# schemFinal.net
KiCad netlist of a schematic drawn in EAGLE
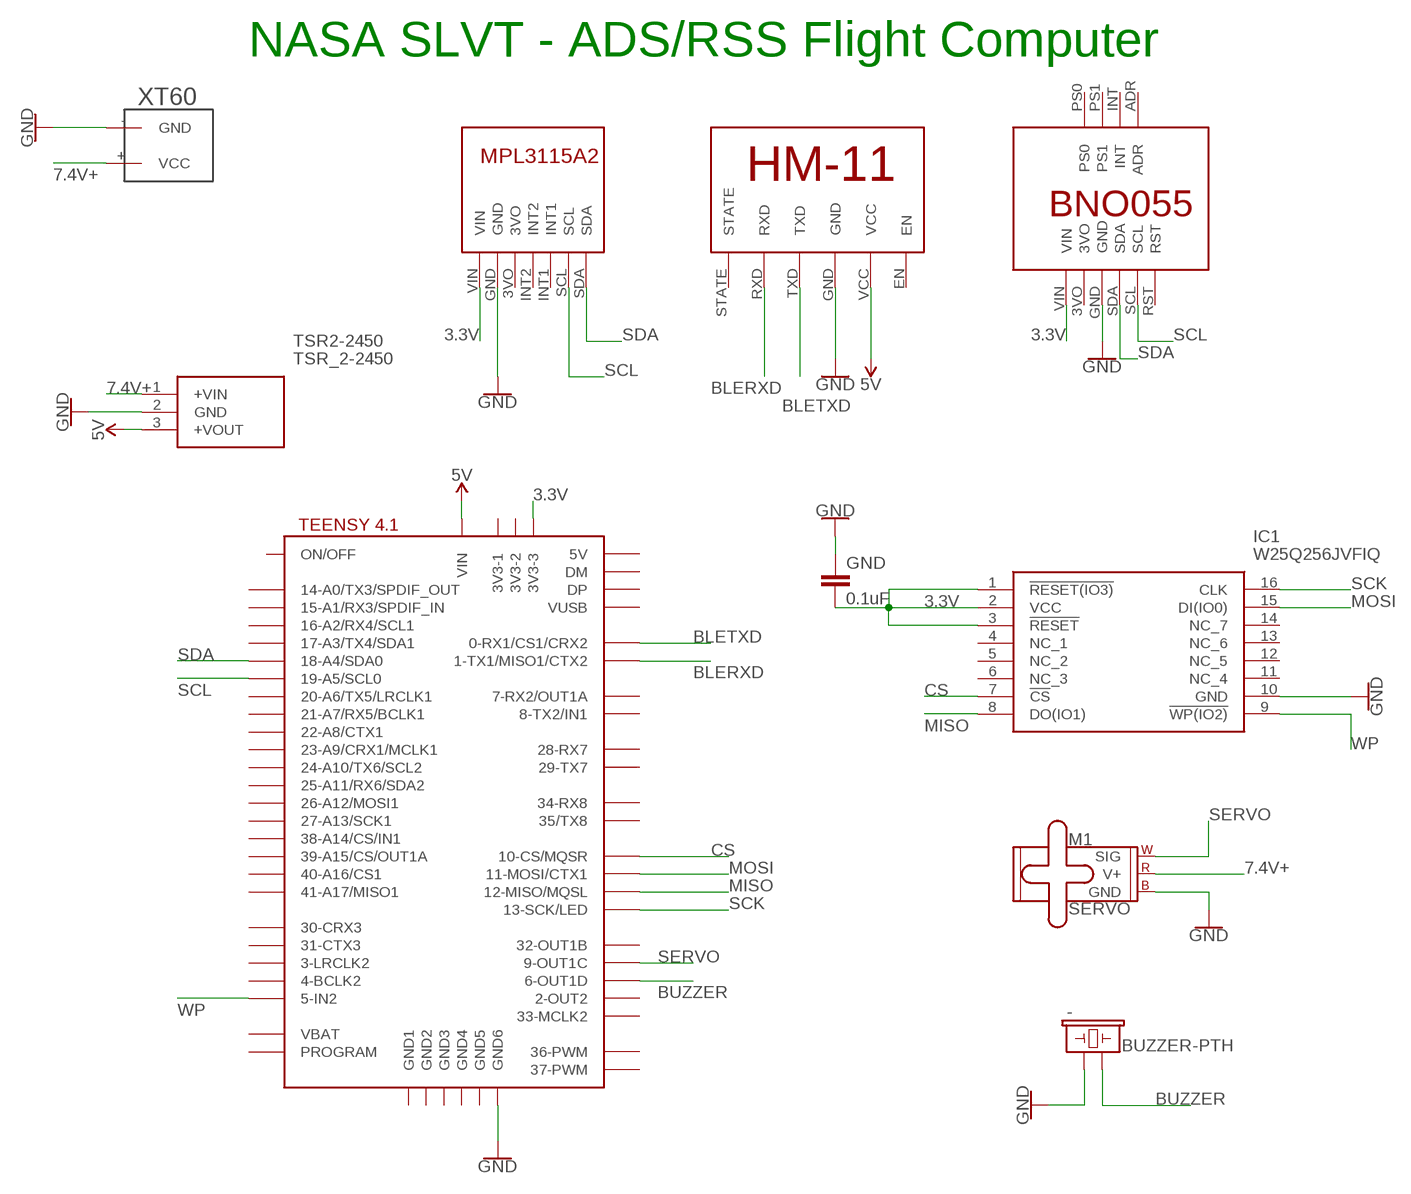
[diagram p0: schematic, sheet 1]

(export (version "E")
  (design (tool "Eeschema 10.0.6"))
  (components
    (comp (ref "-")
      (value "BUZZER-PTH")
      (footprint "eagle-import:BUZZER-12MM")
      (libsource (lib "eagle-import") (part "BUZZER-PTH"))
    )
    (comp (ref "GND")
      (value "0.1uF")
      (footprint "eagle-import:CAP-PTH-2.54")
      (libsource (lib "eagle-import") (part "22PF-PTH-2.54MM-200V-5%"))
    )
    (comp (ref "IC1")
      (value "W25Q256JVFIQ")
      (footprint "eagle-import:SOIC127P1032X264-16N")
      (fields (field (name "MOUSER_PART_NUMBER") "454-W25Q256JVFIQ"))
      (libsource (lib "eagle-import") (part "W25Q256JVFIQ"))
    )
    (comp (ref "M1")
      (value "SERVO")
      (footprint "eagle-import:1X03")
      (libsource (lib "eagle-import") (part "SERVO"))
    )
    (comp (ref "TSR2-2450")
      (value "TSR_2-2450")
      (footprint "eagle-import:TSR-2")
      (fields
        (field (name "MANUFACTURER_PART_NUMBER") "TSR 2-2450")
        (field (name "MOUSER_PART_NUMBER") "495-TSR2-2450")
      )
      (libsource (lib "eagle-import") (part "TSR_2-2450"))
    )
    (comp (ref "U$1")
      (value "BNO055")
      (footprint "eagle-import:BNO055")
      (libsource (lib "eagle-import") (part "BNO055"))
    )
    (comp (ref "U$2")
      (value "MPL3115A2")
      (footprint "eagle-import:MPL3115A2")
      (libsource (lib "eagle-import") (part "MPL3115A2"))
    )
    (comp (ref "U$3")
      (value "TEENSY41-E")
      (footprint "eagle-import:TENNSY41-E")
      (libsource (lib "eagle-import") (part "TEENSY41-E"))
    )
    (comp (ref "U$4")
      (value "HM-11")
      (footprint "eagle-import:HM-11")
      (libsource (lib "eagle-import") (part "HM-11"))
    )
    (comp (ref "U$5")
      (value "XT60")
      (footprint "eagle-import:XT60")
      (libsource (lib "eagle-import") (part "XT60"))
    )
  )
  (nets
    (net (code "1") (name "/3.3V") (class "Default")
      (node (ref "GND") (pin "2") (pinfunction "2_2") (pintype "passive"))
      (node (ref "IC1") (pin "1") (pinfunction "~{RESET(IO3})_1") (pintype "bidirectional"))
      (node (ref "IC1") (pin "2") (pinfunction "VCC_2") (pintype "bidirectional"))
      (node (ref "IC1") (pin "3") (pinfunction "~{RESET}_3") (pintype "bidirectional"))
      (node (ref "U$1") (pin "VIN") (pinfunction "VIN_VIN") (pintype "bidirectional"))
      (node (ref "U$2") (pin "VIN") (pinfunction "VIN_VIN") (pintype "bidirectional"))
      (node (ref "U$3") (pin "3V3-3") (pinfunction "3V3-3_3V3-3") (pintype "bidirectional"))
    )
    (net (code "2") (name "/7.4V+") (class "Default")
      (node (ref "M1") (pin "2") (pinfunction "V+_2") (pintype "bidirectional"))
      (node (ref "TSR2-2450") (pin "1") (pinfunction "+VIN_1") (pintype "input"))
      (node (ref "U$5") (pin "+") (pinfunction "VCC_+") (pintype "bidirectional"))
    )
    (net (code "3") (name "/BLERXD") (class "Default")
      (node (ref "U$3") (pin "1-TX1/MISO1/CTX2") (pinfunction "1-TX1/MISO1/CTX2_1-TX1/MISO1/CTX2") (pintype "bidirectional"))
      (node (ref "U$4") (pin "RXD") (pinfunction "RXD_RXD") (pintype "bidirectional"))
    )
    (net (code "4") (name "/BLETXD") (class "Default")
      (node (ref "U$3") (pin "0-RX1/CS1/CRX2") (pinfunction "0-RX1/CS1/CRX2_0-RX1/CS1/CRX2") (pintype "bidirectional"))
      (node (ref "U$4") (pin "TXD") (pinfunction "TXD_TXD") (pintype "bidirectional"))
    )
    (net (code "5") (name "/BUZZER") (class "Default")
      (node (ref "-") (pin "-") (pinfunction "2_-") (pintype "passive"))
      (node (ref "U$3") (pin "6-OUT1D") (pinfunction "6-OUT1D_6-OUT1D") (pintype "bidirectional"))
    )
    (net (code "6") (name "/CS") (class "Default")
      (node (ref "IC1") (pin "7") (pinfunction "~{CS}_7") (pintype "bidirectional"))
      (node (ref "U$3") (pin "10-CS\\MQSR") (pinfunction "10-CS/MQSR_10-CS\\MQSR") (pintype "bidirectional"))
    )
    (net (code "7") (name "/MISO") (class "Default")
      (node (ref "IC1") (pin "8") (pinfunction "DO(IO1)_8") (pintype "bidirectional"))
      (node (ref "U$3") (pin "12-MISO/MQSL") (pinfunction "12-MISO/MQSL_12-MISO/MQSL") (pintype "bidirectional"))
    )
    (net (code "8") (name "/MOSI") (class "Default")
      (node (ref "IC1") (pin "15") (pinfunction "DI(IO0)_15") (pintype "bidirectional"))
      (node (ref "U$3") (pin "11-MOSI/CTX1") (pinfunction "11-MOSI/CTX1_11-MOSI/CTX1") (pintype "bidirectional"))
    )
    (net (code "9") (name "/SCK") (class "Default")
      (node (ref "IC1") (pin "16") (pinfunction "CLK_16") (pintype "bidirectional"))
      (node (ref "U$3") (pin "13-SCK/LED") (pinfunction "13-SCK/LED_13-SCK/LED") (pintype "bidirectional"))
    )
    (net (code "10") (name "/SCL") (class "Default")
      (node (ref "U$1") (pin "SCL") (pinfunction "SCL_SCL") (pintype "bidirectional"))
      (node (ref "U$2") (pin "SCL") (pinfunction "SCL_SCL") (pintype "bidirectional"))
      (node (ref "U$3") (pin "19-A5/SCL0") (pinfunction "19-A5/SCL0_19-A5/SCL0") (pintype "bidirectional"))
    )
    (net (code "11") (name "/SDA") (class "Default")
      (node (ref "U$1") (pin "SDA") (pinfunction "SDA_SDA") (pintype "bidirectional"))
      (node (ref "U$2") (pin "SDA") (pinfunction "SDA_SDA") (pintype "bidirectional"))
      (node (ref "U$3") (pin "18-A4/SDA0") (pinfunction "18-A4/SDA0_18-A4/SDA0") (pintype "bidirectional"))
    )
    (net (code "12") (name "/SERVO") (class "Default")
      (node (ref "M1") (pin "1") (pinfunction "SIG_1") (pintype "bidirectional"))
      (node (ref "U$3") (pin "9-OUT1C") (pinfunction "9-OUT1C_9-OUT1C") (pintype "bidirectional"))
    )
    (net (code "13") (name "/WP") (class "Default")
      (node (ref "IC1") (pin "9") (pinfunction "~{WP(IO2})_9") (pintype "bidirectional"))
      (node (ref "U$3") (pin "5-IN2") (pinfunction "5-IN2_5-IN2") (pintype "bidirectional"))
    )
    (net (code "14") (name "5V") (class "Default")
      (node (ref "TSR2-2450") (pin "3") (pinfunction "+VOUT_3") (pintype "output"))
      (node (ref "U$3") (pin "VIN") (pinfunction "VIN_VIN") (pintype "bidirectional"))
      (node (ref "U$4") (pin "VCC") (pinfunction "VCC_VCC") (pintype "bidirectional"))
    )
    (net (code "15") (name "GND") (class "Default")
      (node (ref "-") (pin "+") (pinfunction "1_+") (pintype "passive"))
      (node (ref "GND") (pin "1") (pinfunction "1_1") (pintype "passive"))
      (node (ref "IC1") (pin "10") (pinfunction "GND_10") (pintype "bidirectional"))
      (node (ref "M1") (pin "3") (pinfunction "GND_3") (pintype "bidirectional"))
      (node (ref "TSR2-2450") (pin "2") (pinfunction "GND_2") (pintype "power_in"))
      (node (ref "U$1") (pin "GND") (pinfunction "GND_GND") (pintype "bidirectional"))
      (node (ref "U$2") (pin "GND") (pinfunction "GND_GND") (pintype "bidirectional"))
      (node (ref "U$3") (pin "GND6") (pinfunction "GND6_GND6") (pintype "bidirectional"))
      (node (ref "U$4") (pin "GND") (pinfunction "GND_GND") (pintype "bidirectional"))
      (node (ref "U$5") (pin "-") (pinfunction "GND_-") (pintype "bidirectional"))
    )
    (net (code "16") (name "unconnected-(IC1-NC_1-Pad4)") (class "Default")
      (node (ref "IC1") (pin "4") (pinfunction "NC_1_4") (pintype "bidirectional"))
    )
    (net (code "17") (name "unconnected-(IC1-NC_2-Pad5)") (class "Default")
      (node (ref "IC1") (pin "5") (pinfunction "NC_2_5") (pintype "bidirectional"))
    )
    (net (code "18") (name "unconnected-(IC1-NC_3-Pad6)") (class "Default")
      (node (ref "IC1") (pin "6") (pinfunction "NC_3_6") (pintype "bidirectional"))
    )
    (net (code "19") (name "unconnected-(IC1-NC_4-Pad11)") (class "Default")
      (node (ref "IC1") (pin "11") (pinfunction "NC_4_11") (pintype "bidirectional"))
    )
    (net (code "20") (name "unconnected-(IC1-NC_5-Pad12)") (class "Default")
      (node (ref "IC1") (pin "12") (pinfunction "NC_5_12") (pintype "bidirectional"))
    )
    (net (code "21") (name "unconnected-(IC1-NC_6-Pad13)") (class "Default")
      (node (ref "IC1") (pin "13") (pinfunction "NC_6_13") (pintype "bidirectional"))
    )
    (net (code "22") (name "unconnected-(IC1-NC_7-Pad14)") (class "Default")
      (node (ref "IC1") (pin "14") (pinfunction "NC_7_14") (pintype "bidirectional"))
    )
    (net (code "23") (name "unconnected-(U$1-Pad3VO)") (class "Default")
      (node (ref "U$1") (pin "3VO") (pinfunction "3VO_3VO") (pintype "bidirectional"))
    )
    (net (code "24") (name "unconnected-(U$1-PadADR)") (class "Default")
      (node (ref "U$1") (pin "ADR") (pinfunction "ADR_ADR") (pintype "bidirectional"))
    )
    (net (code "25") (name "unconnected-(U$1-PadINT)") (class "Default")
      (node (ref "U$1") (pin "INT") (pinfunction "INT_INT") (pintype "bidirectional"))
    )
    (net (code "26") (name "unconnected-(U$1-PadPS0)") (class "Default")
      (node (ref "U$1") (pin "PS0") (pinfunction "PS0_PS0") (pintype "bidirectional"))
    )
    (net (code "27") (name "unconnected-(U$1-PadPS1)") (class "Default")
      (node (ref "U$1") (pin "PS1") (pinfunction "PS1_PS1") (pintype "bidirectional"))
    )
    (net (code "28") (name "unconnected-(U$1-PadRST)") (class "Default")
      (node (ref "U$1") (pin "RST") (pinfunction "RST_RST") (pintype "bidirectional"))
    )
    (net (code "29") (name "unconnected-(U$2-Pad3VO)") (class "Default")
      (node (ref "U$2") (pin "3VO") (pinfunction "3VO_3VO") (pintype "bidirectional"))
    )
    (net (code "30") (name "unconnected-(U$2-PadINT1)") (class "Default")
      (node (ref "U$2") (pin "INT1") (pinfunction "INT1_INT1") (pintype "bidirectional"))
    )
    (net (code "31") (name "unconnected-(U$2-PadINT2)") (class "Default")
      (node (ref "U$2") (pin "INT2") (pinfunction "INT2_INT2") (pintype "bidirectional"))
    )
    (net (code "32") (name "unconnected-(U$3-5V-Pad+5V)") (class "Default")
      (node (ref "U$3") (pin "+5V") (pinfunction "5V_+5V") (pintype "bidirectional"))
    )
    (net (code "33") (name "unconnected-(U$3-35{slash}TX8-Pad35-TX8)") (class "Default")
      (node (ref "U$3") (pin "35-TX8") (pinfunction "35/TX8_35-TX8") (pintype "bidirectional"))
    )
    (net (code "34") (name "unconnected-(U$3-Pad2-OUT2)") (class "Default")
      (node (ref "U$3") (pin "2-OUT2") (pinfunction "2-OUT2_2-OUT2") (pintype "bidirectional"))
    )
    (net (code "35") (name "unconnected-(U$3-Pad3-LRCLK2)") (class "Default")
      (node (ref "U$3") (pin "3-LRCLK2") (pinfunction "3-LRCLK2_3-LRCLK2") (pintype "bidirectional"))
    )
    (net (code "36") (name "unconnected-(U$3-Pad3V3-1)") (class "Default")
      (node (ref "U$3") (pin "3V3-1") (pinfunction "3V3-1_3V3-1") (pintype "bidirectional"))
    )
    (net (code "37") (name "unconnected-(U$3-Pad3V3-2)") (class "Default")
      (node (ref "U$3") (pin "3V3-2") (pinfunction "3V3-2_3V3-2") (pintype "bidirectional"))
    )
    (net (code "38") (name "unconnected-(U$3-Pad4-BCLK2)") (class "Default")
      (node (ref "U$3") (pin "4-BCLK2") (pinfunction "4-BCLK2_4-BCLK2") (pintype "bidirectional"))
    )
    (net (code "39") (name "unconnected-(U$3-Pad7-RX2{slash}OUT1A)") (class "Default")
      (node (ref "U$3") (pin "7-RX2/OUT1A") (pinfunction "7-RX2/OUT1A_7-RX2/OUT1A") (pintype "bidirectional"))
    )
    (net (code "40") (name "unconnected-(U$3-Pad8-TX2{slash}IN1)") (class "Default")
      (node (ref "U$3") (pin "8-TX2/IN1") (pinfunction "8-TX2/IN1_8-TX2/IN1") (pintype "bidirectional"))
    )
    (net (code "41") (name "unconnected-(U$3-Pad14-A0{slash}TX3{slash}SPDIF_OUT)") (class "Default")
      (node (ref "U$3") (pin "14-A0/TX3/SPDIF_OUT") (pinfunction "14-A0/TX3/SPDIF_OUT_14-A0/TX3/SPDIF_OUT") (pintype "bidirectional"))
    )
    (net (code "42") (name "unconnected-(U$3-Pad15-A1{slash}RX3{slash}SPDIF_IN)") (class "Default")
      (node (ref "U$3") (pin "15-A1/RX3/SPDIF_IN") (pinfunction "15-A1/RX3/SPDIF_IN_15-A1/RX3/SPDIF_IN") (pintype "bidirectional"))
    )
    (net (code "43") (name "unconnected-(U$3-Pad16-A2{slash}RX4{slash}SCL1)") (class "Default")
      (node (ref "U$3") (pin "16-A2/RX4/SCL1") (pinfunction "16-A2/RX4/SCL1_16-A2/RX4/SCL1") (pintype "bidirectional"))
    )
    (net (code "44") (name "unconnected-(U$3-Pad17-A3{slash}TX4{slash}SDA1)") (class "Default")
      (node (ref "U$3") (pin "17-A3/TX4/SDA1") (pinfunction "17-A3/TX4/SDA1_17-A3/TX4/SDA1") (pintype "bidirectional"))
    )
    (net (code "45") (name "unconnected-(U$3-Pad20-A6{slash}TX5{slash}LRCLK1)") (class "Default")
      (node (ref "U$3") (pin "20-A6/TX5/LRCLK1") (pinfunction "20-A6/TX5/LRCLK1_20-A6/TX5/LRCLK1") (pintype "bidirectional"))
    )
    (net (code "46") (name "unconnected-(U$3-Pad21-A7{slash}RX5{slash}BCLK1)") (class "Default")
      (node (ref "U$3") (pin "21-A7/RX5/BCLK1") (pinfunction "21-A7/RX5/BCLK1_21-A7/RX5/BCLK1") (pintype "bidirectional"))
    )
    (net (code "47") (name "unconnected-(U$3-Pad22-A8{slash}CTX1)") (class "Default")
      (node (ref "U$3") (pin "22-A8/CTX1") (pinfunction "22-A8/CTX1_22-A8/CTX1") (pintype "bidirectional"))
    )
    (net (code "48") (name "unconnected-(U$3-Pad23-A9{slash}CRX1{slash}MCLK1)") (class "Default")
      (node (ref "U$3") (pin "23-A9/CRX1/MCLK1") (pinfunction "23-A9/CRX1/MCLK1_23-A9/CRX1/MCLK1") (pintype "bidirectional"))
    )
    (net (code "49") (name "unconnected-(U$3-Pad24-A10{slash}TX6{slash}SCL2)") (class "Default")
      (node (ref "U$3") (pin "24-A10/TX6/SCL2") (pinfunction "24-A10/TX6/SCL2_24-A10/TX6/SCL2") (pintype "bidirectional"))
    )
    (net (code "50") (name "unconnected-(U$3-Pad25-A11{slash}RX6{slash}SDA2)") (class "Default")
      (node (ref "U$3") (pin "25-A11/RX6/SDA2") (pinfunction "25-A11/RX6/SDA2_25-A11/RX6/SDA2") (pintype "bidirectional"))
    )
    (net (code "51") (name "unconnected-(U$3-Pad26-A12{slash}MOSI1)") (class "Default")
      (node (ref "U$3") (pin "26-A12/MOSI1") (pinfunction "26-A12/MOSI1_26-A12/MOSI1") (pintype "bidirectional"))
    )
    (net (code "52") (name "unconnected-(U$3-Pad27-A13{slash}SCK1)") (class "Default")
      (node (ref "U$3") (pin "27-A13/SCK1") (pinfunction "27-A13/SCK1_27-A13/SCK1") (pintype "bidirectional"))
    )
    (net (code "53") (name "unconnected-(U$3-Pad28-RX7)") (class "Default")
      (node (ref "U$3") (pin "28-RX7") (pinfunction "28-RX7_28-RX7") (pintype "bidirectional"))
    )
    (net (code "54") (name "unconnected-(U$3-Pad29-TX7)") (class "Default")
      (node (ref "U$3") (pin "29-TX7") (pinfunction "29-TX7_29-TX7") (pintype "bidirectional"))
    )
    (net (code "55") (name "unconnected-(U$3-Pad30-CRX3)") (class "Default")
      (node (ref "U$3") (pin "30-CRX3") (pinfunction "30-CRX3_30-CRX3") (pintype "bidirectional"))
    )
    (net (code "56") (name "unconnected-(U$3-Pad31-CTX3)") (class "Default")
      (node (ref "U$3") (pin "31-CTX3") (pinfunction "31-CTX3_31-CTX3") (pintype "bidirectional"))
    )
    (net (code "57") (name "unconnected-(U$3-Pad32-OUT1B)") (class "Default")
      (node (ref "U$3") (pin "32-OUT1B") (pinfunction "32-OUT1B_32-OUT1B") (pintype "bidirectional"))
    )
    (net (code "58") (name "unconnected-(U$3-Pad33-MCLK2)") (class "Default")
      (node (ref "U$3") (pin "33-MCLK2") (pinfunction "33-MCLK2_33-MCLK2") (pintype "bidirectional"))
    )
    (net (code "59") (name "unconnected-(U$3-Pad34-RX8)") (class "Default")
      (node (ref "U$3") (pin "34-RX8") (pinfunction "34-RX8_34-RX8") (pintype "bidirectional"))
    )
    (net (code "60") (name "unconnected-(U$3-Pad36-PWM)") (class "Default")
      (node (ref "U$3") (pin "36-PWM") (pinfunction "36-PWM_36-PWM") (pintype "bidirectional"))
    )
    (net (code "61") (name "unconnected-(U$3-Pad37-PWM)") (class "Default")
      (node (ref "U$3") (pin "37-PWM") (pinfunction "37-PWM_37-PWM") (pintype "bidirectional"))
    )
    (net (code "62") (name "unconnected-(U$3-Pad38-A14{slash}CS{slash}IN1)") (class "Default")
      (node (ref "U$3") (pin "38-A14/CS/IN1") (pinfunction "38-A14/CS/IN1_38-A14/CS/IN1") (pintype "bidirectional"))
    )
    (net (code "63") (name "unconnected-(U$3-Pad39-A15{slash}CS{slash}OUT1A)") (class "Default")
      (node (ref "U$3") (pin "39-A15/CS/OUT1A") (pinfunction "39-A15/CS/OUT1A_39-A15/CS/OUT1A") (pintype "bidirectional"))
    )
    (net (code "64") (name "unconnected-(U$3-Pad40-A16{slash}CS1)") (class "Default")
      (node (ref "U$3") (pin "40-A16/CS1") (pinfunction "40-A16/CS1_40-A16/CS1") (pintype "bidirectional"))
    )
    (net (code "65") (name "unconnected-(U$3-Pad41-A17{slash}MISO1)") (class "Default")
      (node (ref "U$3") (pin "41-A17/MISO1") (pinfunction "41-A17/MISO1_41-A17/MISO1") (pintype "bidirectional"))
    )
    (net (code "66") (name "unconnected-(U$3-PadDM)") (class "Default")
      (node (ref "U$3") (pin "DM") (pinfunction "DM_DM") (pintype "bidirectional"))
    )
    (net (code "67") (name "unconnected-(U$3-PadDP)") (class "Default")
      (node (ref "U$3") (pin "DP") (pinfunction "DP_DP") (pintype "bidirectional"))
    )
    (net (code "68") (name "unconnected-(U$3-PadGND1)") (class "Default")
      (node (ref "U$3") (pin "GND1") (pinfunction "GND1_GND1") (pintype "bidirectional"))
    )
    (net (code "69") (name "unconnected-(U$3-PadGND2)") (class "Default")
      (node (ref "U$3") (pin "GND2") (pinfunction "GND2_GND2") (pintype "bidirectional"))
    )
    (net (code "70") (name "unconnected-(U$3-PadGND3)") (class "Default")
      (node (ref "U$3") (pin "GND3") (pinfunction "GND3_GND3") (pintype "bidirectional"))
    )
    (net (code "71") (name "unconnected-(U$3-PadGND4)") (class "Default")
      (node (ref "U$3") (pin "GND4") (pinfunction "GND4_GND4") (pintype "bidirectional"))
    )
    (net (code "72") (name "unconnected-(U$3-PadGND5)") (class "Default")
      (node (ref "U$3") (pin "GND5") (pinfunction "GND5_GND5") (pintype "bidirectional"))
    )
    (net (code "73") (name "unconnected-(U$3-PadON{slash}OFF)") (class "Default")
      (node (ref "U$3") (pin "ON/OFF") (pinfunction "ON/OFF_ON/OFF") (pintype "bidirectional"))
    )
    (net (code "74") (name "unconnected-(U$3-PadPROGRAM)") (class "Default")
      (node (ref "U$3") (pin "PROGRAM") (pinfunction "PROGRAM_PROGRAM") (pintype "bidirectional"))
    )
    (net (code "75") (name "unconnected-(U$3-PadVBAT)") (class "Default")
      (node (ref "U$3") (pin "VBAT") (pinfunction "VBAT_VBAT") (pintype "bidirectional"))
    )
    (net (code "76") (name "unconnected-(U$3-PadVUSB)") (class "Default")
      (node (ref "U$3") (pin "VUSB") (pinfunction "VUSB_VUSB") (pintype "bidirectional"))
    )
    (net (code "77") (name "unconnected-(U$4-PadEN)") (class "Default")
      (node (ref "U$4") (pin "EN") (pinfunction "EN_EN") (pintype "bidirectional"))
    )
    (net (code "78") (name "unconnected-(U$4-PadSTATE)") (class "Default")
      (node (ref "U$4") (pin "STATE") (pinfunction "STATE_STATE") (pintype "bidirectional"))
    )
  )
)
